# leds.net
KiCad netlist of a schematic drawn in Altium Designer
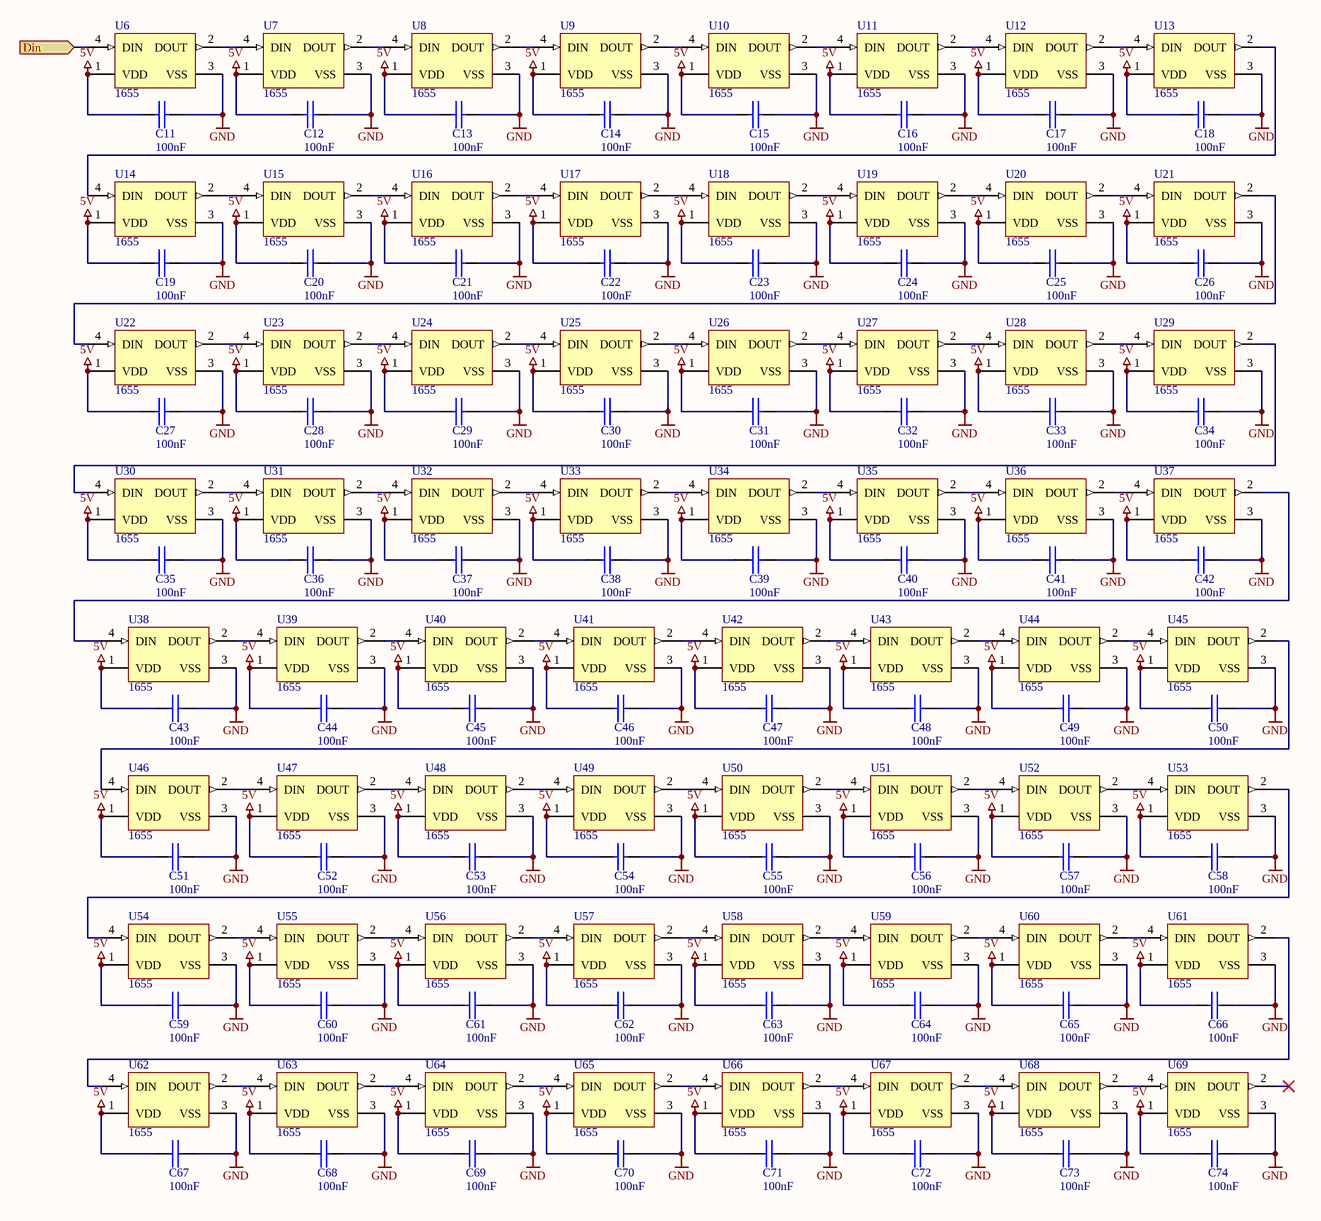
[diagram p0: leds.SchDoc]

(export (version "E")
  (design (tool "Eeschema 10.0.6"))
  (components
    (comp (ref "C11") (value "100nF") (footprint "Cap_0805") (libsource (lib "*") (part "C")))
    (comp (ref "C12") (value "100nF") (footprint "Cap_0805") (libsource (lib "*") (part "C")))
    (comp (ref "C13") (value "100nF") (footprint "Cap_0805") (libsource (lib "*") (part "C")))
    (comp (ref "C14") (value "100nF") (footprint "Cap_0805") (libsource (lib "*") (part "C")))
    (comp (ref "C15") (value "100nF") (footprint "Cap_0805") (libsource (lib "*") (part "C")))
    (comp (ref "C16") (value "100nF") (footprint "Cap_0805") (libsource (lib "*") (part "C")))
    (comp (ref "C17") (value "100nF") (footprint "Cap_0805") (libsource (lib "*") (part "C")))
    (comp (ref "C18") (value "100nF") (footprint "Cap_0805") (libsource (lib "*") (part "C")))
    (comp (ref "C19") (value "100nF") (footprint "Cap_0805") (libsource (lib "*") (part "C")))
    (comp (ref "C20") (value "100nF") (footprint "Cap_0805") (libsource (lib "*") (part "C")))
    (comp (ref "C21") (value "100nF") (footprint "Cap_0805") (libsource (lib "*") (part "C")))
    (comp (ref "C22") (value "100nF") (footprint "Cap_0805") (libsource (lib "*") (part "C")))
    (comp (ref "C23") (value "100nF") (footprint "Cap_0805") (libsource (lib "*") (part "C")))
    (comp (ref "C24") (value "100nF") (footprint "Cap_0805") (libsource (lib "*") (part "C")))
    (comp (ref "C25") (value "100nF") (footprint "Cap_0805") (libsource (lib "*") (part "C")))
    (comp (ref "C26") (value "100nF") (footprint "Cap_0805") (libsource (lib "*") (part "C")))
    (comp (ref "C27") (value "100nF") (footprint "Cap_0805") (libsource (lib "*") (part "C")))
    (comp (ref "C28") (value "100nF") (footprint "Cap_0805") (libsource (lib "*") (part "C")))
    (comp (ref "C29") (value "100nF") (footprint "Cap_0805") (libsource (lib "*") (part "C")))
    (comp (ref "C30") (value "100nF") (footprint "Cap_0805") (libsource (lib "*") (part "C")))
    (comp (ref "C31") (value "100nF") (footprint "Cap_0805") (libsource (lib "*") (part "C")))
    (comp (ref "C32") (value "100nF") (footprint "Cap_0805") (libsource (lib "*") (part "C")))
    (comp (ref "C33") (value "100nF") (footprint "Cap_0805") (libsource (lib "*") (part "C")))
    (comp (ref "C34") (value "100nF") (footprint "Cap_0805") (libsource (lib "*") (part "C")))
    (comp (ref "C35") (value "100nF") (footprint "Cap_0805") (libsource (lib "*") (part "C")))
    (comp (ref "C36") (value "100nF") (footprint "Cap_0805") (libsource (lib "*") (part "C")))
    (comp (ref "C37") (value "100nF") (footprint "Cap_0805") (libsource (lib "*") (part "C")))
    (comp (ref "C38") (value "100nF") (footprint "Cap_0805") (libsource (lib "*") (part "C")))
    (comp (ref "C39") (value "100nF") (footprint "Cap_0805") (libsource (lib "*") (part "C")))
    (comp (ref "C40") (value "100nF") (footprint "Cap_0805") (libsource (lib "*") (part "C")))
    (comp (ref "C41") (value "100nF") (footprint "Cap_0805") (libsource (lib "*") (part "C")))
    (comp (ref "C42") (value "100nF") (footprint "Cap_0805") (libsource (lib "*") (part "C")))
    (comp (ref "C43") (value "100nF") (footprint "Cap_0805") (libsource (lib "*") (part "C")))
    (comp (ref "C44") (value "100nF") (footprint "Cap_0805") (libsource (lib "*") (part "C")))
    (comp (ref "C45") (value "100nF") (footprint "Cap_0805") (libsource (lib "*") (part "C")))
    (comp (ref "C46") (value "100nF") (footprint "Cap_0805") (libsource (lib "*") (part "C")))
    (comp (ref "C47") (value "100nF") (footprint "Cap_0805") (libsource (lib "*") (part "C")))
    (comp (ref "C48") (value "100nF") (footprint "Cap_0805") (libsource (lib "*") (part "C")))
    (comp (ref "C49") (value "100nF") (footprint "Cap_0805") (libsource (lib "*") (part "C")))
    (comp (ref "C50") (value "100nF") (footprint "Cap_0805") (libsource (lib "*") (part "C")))
    (comp (ref "C51") (value "100nF") (footprint "Cap_0805") (libsource (lib "*") (part "C")))
    (comp (ref "C52") (value "100nF") (footprint "Cap_0805") (libsource (lib "*") (part "C")))
    (comp (ref "C53") (value "100nF") (footprint "Cap_0805") (libsource (lib "*") (part "C")))
    (comp (ref "C54") (value "100nF") (footprint "Cap_0805") (libsource (lib "*") (part "C")))
    (comp (ref "C55") (value "100nF") (footprint "Cap_0805") (libsource (lib "*") (part "C")))
    (comp (ref "C56") (value "100nF") (footprint "Cap_0805") (libsource (lib "*") (part "C")))
    (comp (ref "C57") (value "100nF") (footprint "Cap_0805") (libsource (lib "*") (part "C")))
    (comp (ref "C58") (value "100nF") (footprint "Cap_0805") (libsource (lib "*") (part "C")))
    (comp (ref "C59") (value "100nF") (footprint "Cap_0805") (libsource (lib "*") (part "C")))
    (comp (ref "C60") (value "100nF") (footprint "Cap_0805") (libsource (lib "*") (part "C")))
    (comp (ref "C61") (value "100nF") (footprint "Cap_0805") (libsource (lib "*") (part "C")))
    (comp (ref "C62") (value "100nF") (footprint "Cap_0805") (libsource (lib "*") (part "C")))
    (comp (ref "C63") (value "100nF") (footprint "Cap_0805") (libsource (lib "*") (part "C")))
    (comp (ref "C64") (value "100nF") (footprint "Cap_0805") (libsource (lib "*") (part "C")))
    (comp (ref "C65") (value "100nF") (footprint "Cap_0805") (libsource (lib "*") (part "C")))
    (comp (ref "C66") (value "100nF") (footprint "Cap_0805") (libsource (lib "*") (part "C")))
    (comp (ref "C67") (value "100nF") (footprint "Cap_0805") (libsource (lib "*") (part "C")))
    (comp (ref "C68") (value "100nF") (footprint "Cap_0805") (libsource (lib "*") (part "C")))
    (comp (ref "C69") (value "100nF") (footprint "Cap_0805") (libsource (lib "*") (part "C")))
    (comp (ref "C70") (value "100nF") (footprint "Cap_0805") (libsource (lib "*") (part "C")))
    (comp (ref "C71") (value "100nF") (footprint "Cap_0805") (libsource (lib "*") (part "C")))
    (comp (ref "C72") (value "100nF") (footprint "Cap_0805") (libsource (lib "*") (part "C")))
    (comp (ref "C73") (value "100nF") (footprint "Cap_0805") (libsource (lib "*") (part "C")))
    (comp (ref "C74") (value "100nF") (footprint "Cap_0805") (libsource (lib "*") (part "C")))
    (comp (ref "U6")
      (value "1655")
      (footprint "ADA-RGB-1655_V")
      (fields (field (name "MANUFACTURER") "Adafruit-Industries-LLC"))
      (libsource (lib "Altium Content Vault") (part "ADA-RGB-1655-4"))
    )
    (comp (ref "U7")
      (value "1655")
      (footprint "ADA-RGB-1655_V")
      (fields (field (name "MANUFACTURER") "Adafruit-Industries-LLC"))
      (libsource (lib "Altium Content Vault") (part "ADA-RGB-1655-4"))
    )
    (comp (ref "U8")
      (value "1655")
      (footprint "ADA-RGB-1655_V")
      (fields (field (name "MANUFACTURER") "Adafruit-Industries-LLC"))
      (libsource (lib "Altium Content Vault") (part "ADA-RGB-1655-4"))
    )
    (comp (ref "U9")
      (value "1655")
      (footprint "ADA-RGB-1655_V")
      (fields (field (name "MANUFACTURER") "Adafruit-Industries-LLC"))
      (libsource (lib "Altium Content Vault") (part "ADA-RGB-1655-4"))
    )
    (comp (ref "U10")
      (value "1655")
      (footprint "ADA-RGB-1655_V")
      (fields (field (name "MANUFACTURER") "Adafruit-Industries-LLC"))
      (libsource (lib "Altium Content Vault") (part "ADA-RGB-1655-4"))
    )
    (comp (ref "U11")
      (value "1655")
      (footprint "ADA-RGB-1655_V")
      (fields (field (name "MANUFACTURER") "Adafruit-Industries-LLC"))
      (libsource (lib "Altium Content Vault") (part "ADA-RGB-1655-4"))
    )
    (comp (ref "U12")
      (value "1655")
      (footprint "ADA-RGB-1655_V")
      (fields (field (name "MANUFACTURER") "Adafruit-Industries-LLC"))
      (libsource (lib "Altium Content Vault") (part "ADA-RGB-1655-4"))
    )
    (comp (ref "U13")
      (value "1655")
      (footprint "ADA-RGB-1655_V")
      (fields (field (name "MANUFACTURER") "Adafruit-Industries-LLC"))
      (libsource (lib "Altium Content Vault") (part "ADA-RGB-1655-4"))
    )
    (comp (ref "U14")
      (value "1655")
      (footprint "ADA-RGB-1655_V")
      (fields (field (name "MANUFACTURER") "Adafruit-Industries-LLC"))
      (libsource (lib "Altium Content Vault") (part "ADA-RGB-1655-4"))
    )
    (comp (ref "U15")
      (value "1655")
      (footprint "ADA-RGB-1655_V")
      (fields (field (name "MANUFACTURER") "Adafruit-Industries-LLC"))
      (libsource (lib "Altium Content Vault") (part "ADA-RGB-1655-4"))
    )
    (comp (ref "U16")
      (value "1655")
      (footprint "ADA-RGB-1655_V")
      (fields (field (name "MANUFACTURER") "Adafruit-Industries-LLC"))
      (libsource (lib "Altium Content Vault") (part "ADA-RGB-1655-4"))
    )
    (comp (ref "U17")
      (value "1655")
      (footprint "ADA-RGB-1655_V")
      (fields (field (name "MANUFACTURER") "Adafruit-Industries-LLC"))
      (libsource (lib "Altium Content Vault") (part "ADA-RGB-1655-4"))
    )
    (comp (ref "U18")
      (value "1655")
      (footprint "ADA-RGB-1655_V")
      (fields (field (name "MANUFACTURER") "Adafruit-Industries-LLC"))
      (libsource (lib "Altium Content Vault") (part "ADA-RGB-1655-4"))
    )
    (comp (ref "U19")
      (value "1655")
      (footprint "ADA-RGB-1655_V")
      (fields (field (name "MANUFACTURER") "Adafruit-Industries-LLC"))
      (libsource (lib "Altium Content Vault") (part "ADA-RGB-1655-4"))
    )
    (comp (ref "U20")
      (value "1655")
      (footprint "ADA-RGB-1655_V")
      (fields (field (name "MANUFACTURER") "Adafruit-Industries-LLC"))
      (libsource (lib "Altium Content Vault") (part "ADA-RGB-1655-4"))
    )
    (comp (ref "U21")
      (value "1655")
      (footprint "ADA-RGB-1655_V")
      (fields (field (name "MANUFACTURER") "Adafruit-Industries-LLC"))
      (libsource (lib "Altium Content Vault") (part "ADA-RGB-1655-4"))
    )
    (comp (ref "U22")
      (value "1655")
      (footprint "ADA-RGB-1655_V")
      (fields (field (name "MANUFACTURER") "Adafruit-Industries-LLC"))
      (libsource (lib "Altium Content Vault") (part "ADA-RGB-1655-4"))
    )
    (comp (ref "U23")
      (value "1655")
      (footprint "ADA-RGB-1655_V")
      (fields (field (name "MANUFACTURER") "Adafruit-Industries-LLC"))
      (libsource (lib "Altium Content Vault") (part "ADA-RGB-1655-4"))
    )
    (comp (ref "U24")
      (value "1655")
      (footprint "ADA-RGB-1655_V")
      (fields (field (name "MANUFACTURER") "Adafruit-Industries-LLC"))
      (libsource (lib "Altium Content Vault") (part "ADA-RGB-1655-4"))
    )
    (comp (ref "U25")
      (value "1655")
      (footprint "ADA-RGB-1655_V")
      (fields (field (name "MANUFACTURER") "Adafruit-Industries-LLC"))
      (libsource (lib "Altium Content Vault") (part "ADA-RGB-1655-4"))
    )
    (comp (ref "U26")
      (value "1655")
      (footprint "ADA-RGB-1655_V")
      (fields (field (name "MANUFACTURER") "Adafruit-Industries-LLC"))
      (libsource (lib "Altium Content Vault") (part "ADA-RGB-1655-4"))
    )
    (comp (ref "U27")
      (value "1655")
      (footprint "ADA-RGB-1655_V")
      (fields (field (name "MANUFACTURER") "Adafruit-Industries-LLC"))
      (libsource (lib "Altium Content Vault") (part "ADA-RGB-1655-4"))
    )
    (comp (ref "U28")
      (value "1655")
      (footprint "ADA-RGB-1655_V")
      (fields (field (name "MANUFACTURER") "Adafruit-Industries-LLC"))
      (libsource (lib "Altium Content Vault") (part "ADA-RGB-1655-4"))
    )
    (comp (ref "U29")
      (value "1655")
      (footprint "ADA-RGB-1655_V")
      (fields (field (name "MANUFACTURER") "Adafruit-Industries-LLC"))
      (libsource (lib "Altium Content Vault") (part "ADA-RGB-1655-4"))
    )
    (comp (ref "U30")
      (value "1655")
      (footprint "ADA-RGB-1655_V")
      (fields (field (name "MANUFACTURER") "Adafruit-Industries-LLC"))
      (libsource (lib "Altium Content Vault") (part "ADA-RGB-1655-4"))
    )
    (comp (ref "U31")
      (value "1655")
      (footprint "ADA-RGB-1655_V")
      (fields (field (name "MANUFACTURER") "Adafruit-Industries-LLC"))
      (libsource (lib "Altium Content Vault") (part "ADA-RGB-1655-4"))
    )
    (comp (ref "U32")
      (value "1655")
      (footprint "ADA-RGB-1655_V")
      (fields (field (name "MANUFACTURER") "Adafruit-Industries-LLC"))
      (libsource (lib "Altium Content Vault") (part "ADA-RGB-1655-4"))
    )
    (comp (ref "U33")
      (value "1655")
      (footprint "ADA-RGB-1655_V")
      (fields (field (name "MANUFACTURER") "Adafruit-Industries-LLC"))
      (libsource (lib "Altium Content Vault") (part "ADA-RGB-1655-4"))
    )
    (comp (ref "U34")
      (value "1655")
      (footprint "ADA-RGB-1655_V")
      (fields (field (name "MANUFACTURER") "Adafruit-Industries-LLC"))
      (libsource (lib "Altium Content Vault") (part "ADA-RGB-1655-4"))
    )
    (comp (ref "U35")
      (value "1655")
      (footprint "ADA-RGB-1655_V")
      (fields (field (name "MANUFACTURER") "Adafruit-Industries-LLC"))
      (libsource (lib "Altium Content Vault") (part "ADA-RGB-1655-4"))
    )
    (comp (ref "U36")
      (value "1655")
      (footprint "ADA-RGB-1655_V")
      (fields (field (name "MANUFACTURER") "Adafruit-Industries-LLC"))
      (libsource (lib "Altium Content Vault") (part "ADA-RGB-1655-4"))
    )
    (comp (ref "U37")
      (value "1655")
      (footprint "ADA-RGB-1655_V")
      (fields (field (name "MANUFACTURER") "Adafruit-Industries-LLC"))
      (libsource (lib "Altium Content Vault") (part "ADA-RGB-1655-4"))
    )
    (comp (ref "U38")
      (value "1655")
      (footprint "ADA-RGB-1655_V")
      (fields (field (name "MANUFACTURER") "Adafruit-Industries-LLC"))
      (libsource (lib "Altium Content Vault") (part "ADA-RGB-1655-4"))
    )
    (comp (ref "U39")
      (value "1655")
      (footprint "ADA-RGB-1655_V")
      (fields (field (name "MANUFACTURER") "Adafruit-Industries-LLC"))
      (libsource (lib "Altium Content Vault") (part "ADA-RGB-1655-4"))
    )
    (comp (ref "U40")
      (value "1655")
      (footprint "ADA-RGB-1655_V")
      (fields (field (name "MANUFACTURER") "Adafruit-Industries-LLC"))
      (libsource (lib "Altium Content Vault") (part "ADA-RGB-1655-4"))
    )
    (comp (ref "U41")
      (value "1655")
      (footprint "ADA-RGB-1655_V")
      (fields (field (name "MANUFACTURER") "Adafruit-Industries-LLC"))
      (libsource (lib "Altium Content Vault") (part "ADA-RGB-1655-4"))
    )
    (comp (ref "U42")
      (value "1655")
      (footprint "ADA-RGB-1655_V")
      (fields (field (name "MANUFACTURER") "Adafruit-Industries-LLC"))
      (libsource (lib "Altium Content Vault") (part "ADA-RGB-1655-4"))
    )
    (comp (ref "U43")
      (value "1655")
      (footprint "ADA-RGB-1655_V")
      (fields (field (name "MANUFACTURER") "Adafruit-Industries-LLC"))
      (libsource (lib "Altium Content Vault") (part "ADA-RGB-1655-4"))
    )
    (comp (ref "U44")
      (value "1655")
      (footprint "ADA-RGB-1655_V")
      (fields (field (name "MANUFACTURER") "Adafruit-Industries-LLC"))
      (libsource (lib "Altium Content Vault") (part "ADA-RGB-1655-4"))
    )
    (comp (ref "U45")
      (value "1655")
      (footprint "ADA-RGB-1655_V")
      (fields (field (name "MANUFACTURER") "Adafruit-Industries-LLC"))
      (libsource (lib "Altium Content Vault") (part "ADA-RGB-1655-4"))
    )
    (comp (ref "U46")
      (value "1655")
      (footprint "ADA-RGB-1655_V")
      (fields (field (name "MANUFACTURER") "Adafruit-Industries-LLC"))
      (libsource (lib "Altium Content Vault") (part "ADA-RGB-1655-4"))
    )
    (comp (ref "U47")
      (value "1655")
      (footprint "ADA-RGB-1655_V")
      (fields (field (name "MANUFACTURER") "Adafruit-Industries-LLC"))
      (libsource (lib "Altium Content Vault") (part "ADA-RGB-1655-4"))
    )
    (comp (ref "U48")
      (value "1655")
      (footprint "ADA-RGB-1655_V")
      (fields (field (name "MANUFACTURER") "Adafruit-Industries-LLC"))
      (libsource (lib "Altium Content Vault") (part "ADA-RGB-1655-4"))
    )
    (comp (ref "U49")
      (value "1655")
      (footprint "ADA-RGB-1655_V")
      (fields (field (name "MANUFACTURER") "Adafruit-Industries-LLC"))
      (libsource (lib "Altium Content Vault") (part "ADA-RGB-1655-4"))
    )
    (comp (ref "U50")
      (value "1655")
      (footprint "ADA-RGB-1655_V")
      (fields (field (name "MANUFACTURER") "Adafruit-Industries-LLC"))
      (libsource (lib "Altium Content Vault") (part "ADA-RGB-1655-4"))
    )
    (comp (ref "U51")
      (value "1655")
      (footprint "ADA-RGB-1655_V")
      (fields (field (name "MANUFACTURER") "Adafruit-Industries-LLC"))
      (libsource (lib "Altium Content Vault") (part "ADA-RGB-1655-4"))
    )
    (comp (ref "U52")
      (value "1655")
      (footprint "ADA-RGB-1655_V")
      (fields (field (name "MANUFACTURER") "Adafruit-Industries-LLC"))
      (libsource (lib "Altium Content Vault") (part "ADA-RGB-1655-4"))
    )
    (comp (ref "U53")
      (value "1655")
      (footprint "ADA-RGB-1655_V")
      (fields (field (name "MANUFACTURER") "Adafruit-Industries-LLC"))
      (libsource (lib "Altium Content Vault") (part "ADA-RGB-1655-4"))
    )
    (comp (ref "U54")
      (value "1655")
      (footprint "ADA-RGB-1655_V")
      (fields (field (name "MANUFACTURER") "Adafruit-Industries-LLC"))
      (libsource (lib "Altium Content Vault") (part "ADA-RGB-1655-4"))
    )
    (comp (ref "U55")
      (value "1655")
      (footprint "ADA-RGB-1655_V")
      (fields (field (name "MANUFACTURER") "Adafruit-Industries-LLC"))
      (libsource (lib "Altium Content Vault") (part "ADA-RGB-1655-4"))
    )
    (comp (ref "U56")
      (value "1655")
      (footprint "ADA-RGB-1655_V")
      (fields (field (name "MANUFACTURER") "Adafruit-Industries-LLC"))
      (libsource (lib "Altium Content Vault") (part "ADA-RGB-1655-4"))
    )
    (comp (ref "U57")
      (value "1655")
      (footprint "ADA-RGB-1655_V")
      (fields (field (name "MANUFACTURER") "Adafruit-Industries-LLC"))
      (libsource (lib "Altium Content Vault") (part "ADA-RGB-1655-4"))
    )
    (comp (ref "U58")
      (value "1655")
      (footprint "ADA-RGB-1655_V")
      (fields (field (name "MANUFACTURER") "Adafruit-Industries-LLC"))
      (libsource (lib "Altium Content Vault") (part "ADA-RGB-1655-4"))
    )
    (comp (ref "U59")
      (value "1655")
      (footprint "ADA-RGB-1655_V")
      (fields (field (name "MANUFACTURER") "Adafruit-Industries-LLC"))
      (libsource (lib "Altium Content Vault") (part "ADA-RGB-1655-4"))
    )
    (comp (ref "U60")
      (value "1655")
      (footprint "ADA-RGB-1655_V")
      (fields (field (name "MANUFACTURER") "Adafruit-Industries-LLC"))
      (libsource (lib "Altium Content Vault") (part "ADA-RGB-1655-4"))
    )
    (comp (ref "U61")
      (value "1655")
      (footprint "ADA-RGB-1655_V")
      (fields (field (name "MANUFACTURER") "Adafruit-Industries-LLC"))
      (libsource (lib "Altium Content Vault") (part "ADA-RGB-1655-4"))
    )
    (comp (ref "U62")
      (value "1655")
      (footprint "ADA-RGB-1655_V")
      (fields (field (name "MANUFACTURER") "Adafruit-Industries-LLC"))
      (libsource (lib "Altium Content Vault") (part "ADA-RGB-1655-4"))
    )
    (comp (ref "U63")
      (value "1655")
      (footprint "ADA-RGB-1655_V")
      (fields (field (name "MANUFACTURER") "Adafruit-Industries-LLC"))
      (libsource (lib "Altium Content Vault") (part "ADA-RGB-1655-4"))
    )
    (comp (ref "U64")
      (value "1655")
      (footprint "ADA-RGB-1655_V")
      (fields (field (name "MANUFACTURER") "Adafruit-Industries-LLC"))
      (libsource (lib "Altium Content Vault") (part "ADA-RGB-1655-4"))
    )
    (comp (ref "U65")
      (value "1655")
      (footprint "ADA-RGB-1655_V")
      (fields (field (name "MANUFACTURER") "Adafruit-Industries-LLC"))
      (libsource (lib "Altium Content Vault") (part "ADA-RGB-1655-4"))
    )
    (comp (ref "U66")
      (value "1655")
      (footprint "ADA-RGB-1655_V")
      (fields (field (name "MANUFACTURER") "Adafruit-Industries-LLC"))
      (libsource (lib "Altium Content Vault") (part "ADA-RGB-1655-4"))
    )
    (comp (ref "U67")
      (value "1655")
      (footprint "ADA-RGB-1655_V")
      (fields (field (name "MANUFACTURER") "Adafruit-Industries-LLC"))
      (libsource (lib "Altium Content Vault") (part "ADA-RGB-1655-4"))
    )
    (comp (ref "U68")
      (value "1655")
      (footprint "ADA-RGB-1655_V")
      (fields (field (name "MANUFACTURER") "Adafruit-Industries-LLC"))
      (libsource (lib "Altium Content Vault") (part "ADA-RGB-1655-4"))
    )
    (comp (ref "U69")
      (value "1655")
      (footprint "ADA-RGB-1655_V")
      (fields (field (name "MANUFACTURER") "Adafruit-Industries-LLC"))
      (libsource (lib "Altium Content Vault") (part "ADA-RGB-1655-4"))
    )
  )
  (nets
    (net (code "1") (name "/Din") (class "Default")
      (node (ref "U6") (pin "4") (pinfunction "DIN_4") (pintype "input"))
    )
    (net (code "2") (name "5V") (class "Default")
      (node (ref "C11") (pin "1") (pinfunction "1_1") (pintype "passive"))
      (node (ref "C12") (pin "1") (pinfunction "1_1") (pintype "passive"))
      (node (ref "C13") (pin "1") (pinfunction "1_1") (pintype "passive"))
      (node (ref "C14") (pin "1") (pinfunction "1_1") (pintype "passive"))
      (node (ref "C15") (pin "1") (pinfunction "1_1") (pintype "passive"))
      (node (ref "C16") (pin "1") (pinfunction "1_1") (pintype "passive"))
      (node (ref "C17") (pin "1") (pinfunction "1_1") (pintype "passive"))
      (node (ref "C18") (pin "1") (pinfunction "1_1") (pintype "passive"))
      (node (ref "C19") (pin "1") (pinfunction "1_1") (pintype "passive"))
      (node (ref "C20") (pin "1") (pinfunction "1_1") (pintype "passive"))
      (node (ref "C21") (pin "1") (pinfunction "1_1") (pintype "passive"))
      (node (ref "C22") (pin "1") (pinfunction "1_1") (pintype "passive"))
      (node (ref "C23") (pin "1") (pinfunction "1_1") (pintype "passive"))
      (node (ref "C24") (pin "1") (pinfunction "1_1") (pintype "passive"))
      (node (ref "C25") (pin "1") (pinfunction "1_1") (pintype "passive"))
      (node (ref "C26") (pin "1") (pinfunction "1_1") (pintype "passive"))
      (node (ref "C27") (pin "1") (pinfunction "1_1") (pintype "passive"))
      (node (ref "C28") (pin "1") (pinfunction "1_1") (pintype "passive"))
      (node (ref "C29") (pin "1") (pinfunction "1_1") (pintype "passive"))
      (node (ref "C30") (pin "1") (pinfunction "1_1") (pintype "passive"))
      (node (ref "C31") (pin "1") (pinfunction "1_1") (pintype "passive"))
      (node (ref "C32") (pin "1") (pinfunction "1_1") (pintype "passive"))
      (node (ref "C33") (pin "1") (pinfunction "1_1") (pintype "passive"))
      (node (ref "C34") (pin "1") (pinfunction "1_1") (pintype "passive"))
      (node (ref "C35") (pin "1") (pinfunction "1_1") (pintype "passive"))
      (node (ref "C36") (pin "1") (pinfunction "1_1") (pintype "passive"))
      (node (ref "C37") (pin "1") (pinfunction "1_1") (pintype "passive"))
      (node (ref "C38") (pin "1") (pinfunction "1_1") (pintype "passive"))
      (node (ref "C39") (pin "1") (pinfunction "1_1") (pintype "passive"))
      (node (ref "C40") (pin "1") (pinfunction "1_1") (pintype "passive"))
      (node (ref "C41") (pin "1") (pinfunction "1_1") (pintype "passive"))
      (node (ref "C42") (pin "1") (pinfunction "1_1") (pintype "passive"))
      (node (ref "C43") (pin "1") (pinfunction "1_1") (pintype "passive"))
      (node (ref "C44") (pin "1") (pinfunction "1_1") (pintype "passive"))
      (node (ref "C45") (pin "1") (pinfunction "1_1") (pintype "passive"))
      (node (ref "C46") (pin "1") (pinfunction "1_1") (pintype "passive"))
      (node (ref "C47") (pin "1") (pinfunction "1_1") (pintype "passive"))
      (node (ref "C48") (pin "1") (pinfunction "1_1") (pintype "passive"))
      (node (ref "C49") (pin "1") (pinfunction "1_1") (pintype "passive"))
      (node (ref "C50") (pin "1") (pinfunction "1_1") (pintype "passive"))
      (node (ref "C51") (pin "1") (pinfunction "1_1") (pintype "passive"))
      (node (ref "C52") (pin "1") (pinfunction "1_1") (pintype "passive"))
      (node (ref "C53") (pin "1") (pinfunction "1_1") (pintype "passive"))
      (node (ref "C54") (pin "1") (pinfunction "1_1") (pintype "passive"))
      (node (ref "C55") (pin "1") (pinfunction "1_1") (pintype "passive"))
      (node (ref "C56") (pin "1") (pinfunction "1_1") (pintype "passive"))
      (node (ref "C57") (pin "1") (pinfunction "1_1") (pintype "passive"))
      (node (ref "C58") (pin "1") (pinfunction "1_1") (pintype "passive"))
      (node (ref "C59") (pin "1") (pinfunction "1_1") (pintype "passive"))
      (node (ref "C60") (pin "1") (pinfunction "1_1") (pintype "passive"))
      (node (ref "C61") (pin "1") (pinfunction "1_1") (pintype "passive"))
      (node (ref "C62") (pin "1") (pinfunction "1_1") (pintype "passive"))
      (node (ref "C63") (pin "1") (pinfunction "1_1") (pintype "passive"))
      (node (ref "C64") (pin "1") (pinfunction "1_1") (pintype "passive"))
      (node (ref "C65") (pin "1") (pinfunction "1_1") (pintype "passive"))
      (node (ref "C66") (pin "1") (pinfunction "1_1") (pintype "passive"))
      (node (ref "C67") (pin "1") (pinfunction "1_1") (pintype "passive"))
      (node (ref "C68") (pin "1") (pinfunction "1_1") (pintype "passive"))
      (node (ref "C69") (pin "1") (pinfunction "1_1") (pintype "passive"))
      (node (ref "C70") (pin "1") (pinfunction "1_1") (pintype "passive"))
      (node (ref "C71") (pin "1") (pinfunction "1_1") (pintype "passive"))
      (node (ref "C72") (pin "1") (pinfunction "1_1") (pintype "passive"))
      (node (ref "C73") (pin "1") (pinfunction "1_1") (pintype "passive"))
      (node (ref "C74") (pin "1") (pinfunction "1_1") (pintype "passive"))
      (node (ref "U10") (pin "1") (pinfunction "VDD_1") (pintype "power_in"))
      (node (ref "U11") (pin "1") (pinfunction "VDD_1") (pintype "power_in"))
      (node (ref "U12") (pin "1") (pinfunction "VDD_1") (pintype "power_in"))
      (node (ref "U13") (pin "1") (pinfunction "VDD_1") (pintype "power_in"))
      (node (ref "U14") (pin "1") (pinfunction "VDD_1") (pintype "power_in"))
      (node (ref "U15") (pin "1") (pinfunction "VDD_1") (pintype "power_in"))
      (node (ref "U16") (pin "1") (pinfunction "VDD_1") (pintype "power_in"))
      (node (ref "U17") (pin "1") (pinfunction "VDD_1") (pintype "power_in"))
      (node (ref "U18") (pin "1") (pinfunction "VDD_1") (pintype "power_in"))
      (node (ref "U19") (pin "1") (pinfunction "VDD_1") (pintype "power_in"))
      (node (ref "U20") (pin "1") (pinfunction "VDD_1") (pintype "power_in"))
      (node (ref "U21") (pin "1") (pinfunction "VDD_1") (pintype "power_in"))
      (node (ref "U22") (pin "1") (pinfunction "VDD_1") (pintype "power_in"))
      (node (ref "U23") (pin "1") (pinfunction "VDD_1") (pintype "power_in"))
      (node (ref "U24") (pin "1") (pinfunction "VDD_1") (pintype "power_in"))
      (node (ref "U25") (pin "1") (pinfunction "VDD_1") (pintype "power_in"))
      (node (ref "U26") (pin "1") (pinfunction "VDD_1") (pintype "power_in"))
      (node (ref "U27") (pin "1") (pinfunction "VDD_1") (pintype "power_in"))
      (node (ref "U28") (pin "1") (pinfunction "VDD_1") (pintype "power_in"))
      (node (ref "U29") (pin "1") (pinfunction "VDD_1") (pintype "power_in"))
      (node (ref "U30") (pin "1") (pinfunction "VDD_1") (pintype "power_in"))
      (node (ref "U31") (pin "1") (pinfunction "VDD_1") (pintype "power_in"))
      (node (ref "U32") (pin "1") (pinfunction "VDD_1") (pintype "power_in"))
      (node (ref "U33") (pin "1") (pinfunction "VDD_1") (pintype "power_in"))
      (node (ref "U34") (pin "1") (pinfunction "VDD_1") (pintype "power_in"))
      (node (ref "U35") (pin "1") (pinfunction "VDD_1") (pintype "power_in"))
      (node (ref "U36") (pin "1") (pinfunction "VDD_1") (pintype "power_in"))
      (node (ref "U37") (pin "1") (pinfunction "VDD_1") (pintype "power_in"))
      (node (ref "U38") (pin "1") (pinfunction "VDD_1") (pintype "power_in"))
      (node (ref "U39") (pin "1") (pinfunction "VDD_1") (pintype "power_in"))
      (node (ref "U40") (pin "1") (pinfunction "VDD_1") (pintype "power_in"))
      (node (ref "U41") (pin "1") (pinfunction "VDD_1") (pintype "power_in"))
      (node (ref "U42") (pin "1") (pinfunction "VDD_1") (pintype "power_in"))
      (node (ref "U43") (pin "1") (pinfunction "VDD_1") (pintype "power_in"))
      (node (ref "U44") (pin "1") (pinfunction "VDD_1") (pintype "power_in"))
      (node (ref "U45") (pin "1") (pinfunction "VDD_1") (pintype "power_in"))
      (node (ref "U46") (pin "1") (pinfunction "VDD_1") (pintype "power_in"))
      (node (ref "U47") (pin "1") (pinfunction "VDD_1") (pintype "power_in"))
      (node (ref "U48") (pin "1") (pinfunction "VDD_1") (pintype "power_in"))
      (node (ref "U49") (pin "1") (pinfunction "VDD_1") (pintype "power_in"))
      (node (ref "U50") (pin "1") (pinfunction "VDD_1") (pintype "power_in"))
      (node (ref "U51") (pin "1") (pinfunction "VDD_1") (pintype "power_in"))
      (node (ref "U52") (pin "1") (pinfunction "VDD_1") (pintype "power_in"))
      (node (ref "U53") (pin "1") (pinfunction "VDD_1") (pintype "power_in"))
      (node (ref "U54") (pin "1") (pinfunction "VDD_1") (pintype "power_in"))
      (node (ref "U55") (pin "1") (pinfunction "VDD_1") (pintype "power_in"))
      (node (ref "U56") (pin "1") (pinfunction "VDD_1") (pintype "power_in"))
      (node (ref "U57") (pin "1") (pinfunction "VDD_1") (pintype "power_in"))
      (node (ref "U58") (pin "1") (pinfunction "VDD_1") (pintype "power_in"))
      (node (ref "U59") (pin "1") (pinfunction "VDD_1") (pintype "power_in"))
      (node (ref "U6") (pin "1") (pinfunction "VDD_1") (pintype "power_in"))
      (node (ref "U60") (pin "1") (pinfunction "VDD_1") (pintype "power_in"))
      (node (ref "U61") (pin "1") (pinfunction "VDD_1") (pintype "power_in"))
      (node (ref "U62") (pin "1") (pinfunction "VDD_1") (pintype "power_in"))
      (node (ref "U63") (pin "1") (pinfunction "VDD_1") (pintype "power_in"))
      (node (ref "U64") (pin "1") (pinfunction "VDD_1") (pintype "power_in"))
      (node (ref "U65") (pin "1") (pinfunction "VDD_1") (pintype "power_in"))
      (node (ref "U66") (pin "1") (pinfunction "VDD_1") (pintype "power_in"))
      (node (ref "U67") (pin "1") (pinfunction "VDD_1") (pintype "power_in"))
      (node (ref "U68") (pin "1") (pinfunction "VDD_1") (pintype "power_in"))
      (node (ref "U69") (pin "1") (pinfunction "VDD_1") (pintype "power_in"))
      (node (ref "U7") (pin "1") (pinfunction "VDD_1") (pintype "power_in"))
      (node (ref "U8") (pin "1") (pinfunction "VDD_1") (pintype "power_in"))
      (node (ref "U9") (pin "1") (pinfunction "VDD_1") (pintype "power_in"))
    )
    (net (code "3") (name "GND") (class "Default")
      (node (ref "C11") (pin "2") (pinfunction "2_2") (pintype "passive"))
      (node (ref "C12") (pin "2") (pinfunction "2_2") (pintype "passive"))
      (node (ref "C13") (pin "2") (pinfunction "2_2") (pintype "passive"))
      (node (ref "C14") (pin "2") (pinfunction "2_2") (pintype "passive"))
      (node (ref "C15") (pin "2") (pinfunction "2_2") (pintype "passive"))
      (node (ref "C16") (pin "2") (pinfunction "2_2") (pintype "passive"))
      (node (ref "C17") (pin "2") (pinfunction "2_2") (pintype "passive"))
      (node (ref "C18") (pin "2") (pinfunction "2_2") (pintype "passive"))
      (node (ref "C19") (pin "2") (pinfunction "2_2") (pintype "passive"))
      (node (ref "C20") (pin "2") (pinfunction "2_2") (pintype "passive"))
      (node (ref "C21") (pin "2") (pinfunction "2_2") (pintype "passive"))
      (node (ref "C22") (pin "2") (pinfunction "2_2") (pintype "passive"))
      (node (ref "C23") (pin "2") (pinfunction "2_2") (pintype "passive"))
      (node (ref "C24") (pin "2") (pinfunction "2_2") (pintype "passive"))
      (node (ref "C25") (pin "2") (pinfunction "2_2") (pintype "passive"))
      (node (ref "C26") (pin "2") (pinfunction "2_2") (pintype "passive"))
      (node (ref "C27") (pin "2") (pinfunction "2_2") (pintype "passive"))
      (node (ref "C28") (pin "2") (pinfunction "2_2") (pintype "passive"))
      (node (ref "C29") (pin "2") (pinfunction "2_2") (pintype "passive"))
      (node (ref "C30") (pin "2") (pinfunction "2_2") (pintype "passive"))
      (node (ref "C31") (pin "2") (pinfunction "2_2") (pintype "passive"))
      (node (ref "C32") (pin "2") (pinfunction "2_2") (pintype "passive"))
      (node (ref "C33") (pin "2") (pinfunction "2_2") (pintype "passive"))
      (node (ref "C34") (pin "2") (pinfunction "2_2") (pintype "passive"))
      (node (ref "C35") (pin "2") (pinfunction "2_2") (pintype "passive"))
      (node (ref "C36") (pin "2") (pinfunction "2_2") (pintype "passive"))
      (node (ref "C37") (pin "2") (pinfunction "2_2") (pintype "passive"))
      (node (ref "C38") (pin "2") (pinfunction "2_2") (pintype "passive"))
      (node (ref "C39") (pin "2") (pinfunction "2_2") (pintype "passive"))
      (node (ref "C40") (pin "2") (pinfunction "2_2") (pintype "passive"))
      (node (ref "C41") (pin "2") (pinfunction "2_2") (pintype "passive"))
      (node (ref "C42") (pin "2") (pinfunction "2_2") (pintype "passive"))
      (node (ref "C43") (pin "2") (pinfunction "2_2") (pintype "passive"))
      (node (ref "C44") (pin "2") (pinfunction "2_2") (pintype "passive"))
      (node (ref "C45") (pin "2") (pinfunction "2_2") (pintype "passive"))
      (node (ref "C46") (pin "2") (pinfunction "2_2") (pintype "passive"))
      (node (ref "C47") (pin "2") (pinfunction "2_2") (pintype "passive"))
      (node (ref "C48") (pin "2") (pinfunction "2_2") (pintype "passive"))
      (node (ref "C49") (pin "2") (pinfunction "2_2") (pintype "passive"))
      (node (ref "C50") (pin "2") (pinfunction "2_2") (pintype "passive"))
      (node (ref "C51") (pin "2") (pinfunction "2_2") (pintype "passive"))
      (node (ref "C52") (pin "2") (pinfunction "2_2") (pintype "passive"))
      (node (ref "C53") (pin "2") (pinfunction "2_2") (pintype "passive"))
      (node (ref "C54") (pin "2") (pinfunction "2_2") (pintype "passive"))
      (node (ref "C55") (pin "2") (pinfunction "2_2") (pintype "passive"))
      (node (ref "C56") (pin "2") (pinfunction "2_2") (pintype "passive"))
      (node (ref "C57") (pin "2") (pinfunction "2_2") (pintype "passive"))
      (node (ref "C58") (pin "2") (pinfunction "2_2") (pintype "passive"))
      (node (ref "C59") (pin "2") (pinfunction "2_2") (pintype "passive"))
      (node (ref "C60") (pin "2") (pinfunction "2_2") (pintype "passive"))
      (node (ref "C61") (pin "2") (pinfunction "2_2") (pintype "passive"))
      (node (ref "C62") (pin "2") (pinfunction "2_2") (pintype "passive"))
      (node (ref "C63") (pin "2") (pinfunction "2_2") (pintype "passive"))
      (node (ref "C64") (pin "2") (pinfunction "2_2") (pintype "passive"))
      (node (ref "C65") (pin "2") (pinfunction "2_2") (pintype "passive"))
      (node (ref "C66") (pin "2") (pinfunction "2_2") (pintype "passive"))
      (node (ref "C67") (pin "2") (pinfunction "2_2") (pintype "passive"))
      (node (ref "C68") (pin "2") (pinfunction "2_2") (pintype "passive"))
      (node (ref "C69") (pin "2") (pinfunction "2_2") (pintype "passive"))
      (node (ref "C70") (pin "2") (pinfunction "2_2") (pintype "passive"))
      (node (ref "C71") (pin "2") (pinfunction "2_2") (pintype "passive"))
      (node (ref "C72") (pin "2") (pinfunction "2_2") (pintype "passive"))
      (node (ref "C73") (pin "2") (pinfunction "2_2") (pintype "passive"))
      (node (ref "C74") (pin "2") (pinfunction "2_2") (pintype "passive"))
      (node (ref "U10") (pin "3") (pinfunction "VSS_3") (pintype "power_in"))
      (node (ref "U11") (pin "3") (pinfunction "VSS_3") (pintype "power_in"))
      (node (ref "U12") (pin "3") (pinfunction "VSS_3") (pintype "power_in"))
      (node (ref "U13") (pin "3") (pinfunction "VSS_3") (pintype "power_in"))
      (node (ref "U14") (pin "3") (pinfunction "VSS_3") (pintype "power_in"))
      (node (ref "U15") (pin "3") (pinfunction "VSS_3") (pintype "power_in"))
      (node (ref "U16") (pin "3") (pinfunction "VSS_3") (pintype "power_in"))
      (node (ref "U17") (pin "3") (pinfunction "VSS_3") (pintype "power_in"))
      (node (ref "U18") (pin "3") (pinfunction "VSS_3") (pintype "power_in"))
      (node (ref "U19") (pin "3") (pinfunction "VSS_3") (pintype "power_in"))
      (node (ref "U20") (pin "3") (pinfunction "VSS_3") (pintype "power_in"))
      (node (ref "U21") (pin "3") (pinfunction "VSS_3") (pintype "power_in"))
      (node (ref "U22") (pin "3") (pinfunction "VSS_3") (pintype "power_in"))
      (node (ref "U23") (pin "3") (pinfunction "VSS_3") (pintype "power_in"))
      (node (ref "U24") (pin "3") (pinfunction "VSS_3") (pintype "power_in"))
      (node (ref "U25") (pin "3") (pinfunction "VSS_3") (pintype "power_in"))
      (node (ref "U26") (pin "3") (pinfunction "VSS_3") (pintype "power_in"))
      (node (ref "U27") (pin "3") (pinfunction "VSS_3") (pintype "power_in"))
      (node (ref "U28") (pin "3") (pinfunction "VSS_3") (pintype "power_in"))
      (node (ref "U29") (pin "3") (pinfunction "VSS_3") (pintype "power_in"))
      (node (ref "U30") (pin "3") (pinfunction "VSS_3") (pintype "power_in"))
      (node (ref "U31") (pin "3") (pinfunction "VSS_3") (pintype "power_in"))
      (node (ref "U32") (pin "3") (pinfunction "VSS_3") (pintype "power_in"))
      (node (ref "U33") (pin "3") (pinfunction "VSS_3") (pintype "power_in"))
      (node (ref "U34") (pin "3") (pinfunction "VSS_3") (pintype "power_in"))
      (node (ref "U35") (pin "3") (pinfunction "VSS_3") (pintype "power_in"))
      (node (ref "U36") (pin "3") (pinfunction "VSS_3") (pintype "power_in"))
      (node (ref "U37") (pin "3") (pinfunction "VSS_3") (pintype "power_in"))
      (node (ref "U38") (pin "3") (pinfunction "VSS_3") (pintype "power_in"))
      (node (ref "U39") (pin "3") (pinfunction "VSS_3") (pintype "power_in"))
      (node (ref "U40") (pin "3") (pinfunction "VSS_3") (pintype "power_in"))
      (node (ref "U41") (pin "3") (pinfunction "VSS_3") (pintype "power_in"))
      (node (ref "U42") (pin "3") (pinfunction "VSS_3") (pintype "power_in"))
      (node (ref "U43") (pin "3") (pinfunction "VSS_3") (pintype "power_in"))
      (node (ref "U44") (pin "3") (pinfunction "VSS_3") (pintype "power_in"))
      (node (ref "U45") (pin "3") (pinfunction "VSS_3") (pintype "power_in"))
      (node (ref "U46") (pin "3") (pinfunction "VSS_3") (pintype "power_in"))
      (node (ref "U47") (pin "3") (pinfunction "VSS_3") (pintype "power_in"))
      (node (ref "U48") (pin "3") (pinfunction "VSS_3") (pintype "power_in"))
      (node (ref "U49") (pin "3") (pinfunction "VSS_3") (pintype "power_in"))
      (node (ref "U50") (pin "3") (pinfunction "VSS_3") (pintype "power_in"))
      (node (ref "U51") (pin "3") (pinfunction "VSS_3") (pintype "power_in"))
      (node (ref "U52") (pin "3") (pinfunction "VSS_3") (pintype "power_in"))
      (node (ref "U53") (pin "3") (pinfunction "VSS_3") (pintype "power_in"))
      (node (ref "U54") (pin "3") (pinfunction "VSS_3") (pintype "power_in"))
      (node (ref "U55") (pin "3") (pinfunction "VSS_3") (pintype "power_in"))
      (node (ref "U56") (pin "3") (pinfunction "VSS_3") (pintype "power_in"))
      (node (ref "U57") (pin "3") (pinfunction "VSS_3") (pintype "power_in"))
      (node (ref "U58") (pin "3") (pinfunction "VSS_3") (pintype "power_in"))
      (node (ref "U59") (pin "3") (pinfunction "VSS_3") (pintype "power_in"))
      (node (ref "U6") (pin "3") (pinfunction "VSS_3") (pintype "power_in"))
      (node (ref "U60") (pin "3") (pinfunction "VSS_3") (pintype "power_in"))
      (node (ref "U61") (pin "3") (pinfunction "VSS_3") (pintype "power_in"))
      (node (ref "U62") (pin "3") (pinfunction "VSS_3") (pintype "power_in"))
      (node (ref "U63") (pin "3") (pinfunction "VSS_3") (pintype "power_in"))
      (node (ref "U64") (pin "3") (pinfunction "VSS_3") (pintype "power_in"))
      (node (ref "U65") (pin "3") (pinfunction "VSS_3") (pintype "power_in"))
      (node (ref "U66") (pin "3") (pinfunction "VSS_3") (pintype "power_in"))
      (node (ref "U67") (pin "3") (pinfunction "VSS_3") (pintype "power_in"))
      (node (ref "U68") (pin "3") (pinfunction "VSS_3") (pintype "power_in"))
      (node (ref "U69") (pin "3") (pinfunction "VSS_3") (pintype "power_in"))
      (node (ref "U7") (pin "3") (pinfunction "VSS_3") (pintype "power_in"))
      (node (ref "U8") (pin "3") (pinfunction "VSS_3") (pintype "power_in"))
      (node (ref "U9") (pin "3") (pinfunction "VSS_3") (pintype "power_in"))
    )
    (net (code "4") (name "Net-(U6-DOUT)") (class "Default")
      (node (ref "U6") (pin "2") (pinfunction "DOUT_2") (pintype "output"))
      (node (ref "U7") (pin "4") (pinfunction "DIN_4") (pintype "input"))
    )
    (net (code "5") (name "Net-(U7-DOUT)") (class "Default")
      (node (ref "U7") (pin "2") (pinfunction "DOUT_2") (pintype "output"))
      (node (ref "U8") (pin "4") (pinfunction "DIN_4") (pintype "input"))
    )
    (net (code "6") (name "Net-(U8-DOUT)") (class "Default")
      (node (ref "U8") (pin "2") (pinfunction "DOUT_2") (pintype "output"))
      (node (ref "U9") (pin "4") (pinfunction "DIN_4") (pintype "input"))
    )
    (net (code "7") (name "Net-(U10-DIN)") (class "Default")
      (node (ref "U10") (pin "4") (pinfunction "DIN_4") (pintype "input"))
      (node (ref "U9") (pin "2") (pinfunction "DOUT_2") (pintype "output"))
    )
    (net (code "8") (name "Net-(U10-DOUT)") (class "Default")
      (node (ref "U10") (pin "2") (pinfunction "DOUT_2") (pintype "output"))
      (node (ref "U11") (pin "4") (pinfunction "DIN_4") (pintype "input"))
    )
    (net (code "9") (name "Net-(U11-DOUT)") (class "Default")
      (node (ref "U11") (pin "2") (pinfunction "DOUT_2") (pintype "output"))
      (node (ref "U12") (pin "4") (pinfunction "DIN_4") (pintype "input"))
    )
    (net (code "10") (name "Net-(U12-DOUT)") (class "Default")
      (node (ref "U12") (pin "2") (pinfunction "DOUT_2") (pintype "output"))
      (node (ref "U13") (pin "4") (pinfunction "DIN_4") (pintype "input"))
    )
    (net (code "11") (name "Net-(U13-DOUT)") (class "Default")
      (node (ref "U13") (pin "2") (pinfunction "DOUT_2") (pintype "output"))
      (node (ref "U14") (pin "4") (pinfunction "DIN_4") (pintype "input"))
    )
    (net (code "12") (name "Net-(U14-DOUT)") (class "Default")
      (node (ref "U14") (pin "2") (pinfunction "DOUT_2") (pintype "output"))
      (node (ref "U15") (pin "4") (pinfunction "DIN_4") (pintype "input"))
    )
    (net (code "13") (name "Net-(U15-DOUT)") (class "Default")
      (node (ref "U15") (pin "2") (pinfunction "DOUT_2") (pintype "output"))
      (node (ref "U16") (pin "4") (pinfunction "DIN_4") (pintype "input"))
    )
    (net (code "14") (name "Net-(U16-DOUT)") (class "Default")
      (node (ref "U16") (pin "2") (pinfunction "DOUT_2") (pintype "output"))
      (node (ref "U17") (pin "4") (pinfunction "DIN_4") (pintype "input"))
    )
    (net (code "15") (name "Net-(U17-DOUT)") (class "Default")
      (node (ref "U17") (pin "2") (pinfunction "DOUT_2") (pintype "output"))
      (node (ref "U18") (pin "4") (pinfunction "DIN_4") (pintype "input"))
    )
    (net (code "16") (name "Net-(U18-DOUT)") (class "Default")
      (node (ref "U18") (pin "2") (pinfunction "DOUT_2") (pintype "output"))
      (node (ref "U19") (pin "4") (pinfunction "DIN_4") (pintype "input"))
    )
    (net (code "17") (name "Net-(U19-DOUT)") (class "Default")
      (node (ref "U19") (pin "2") (pinfunction "DOUT_2") (pintype "output"))
      (node (ref "U20") (pin "4") (pinfunction "DIN_4") (pintype "input"))
    )
    (net (code "18") (name "Net-(U20-DOUT)") (class "Default")
      (node (ref "U20") (pin "2") (pinfunction "DOUT_2") (pintype "output"))
      (node (ref "U21") (pin "4") (pinfunction "DIN_4") (pintype "input"))
    )
    (net (code "19") (name "Net-(U21-DOUT)") (class "Default")
      (node (ref "U21") (pin "2") (pinfunction "DOUT_2") (pintype "output"))
      (node (ref "U22") (pin "4") (pinfunction "DIN_4") (pintype "input"))
    )
    (net (code "20") (name "Net-(U22-DOUT)") (class "Default")
      (node (ref "U22") (pin "2") (pinfunction "DOUT_2") (pintype "output"))
      (node (ref "U23") (pin "4") (pinfunction "DIN_4") (pintype "input"))
    )
    (net (code "21") (name "Net-(U23-DOUT)") (class "Default")
      (node (ref "U23") (pin "2") (pinfunction "DOUT_2") (pintype "output"))
      (node (ref "U24") (pin "4") (pinfunction "DIN_4") (pintype "input"))
    )
    (net (code "22") (name "Net-(U24-DOUT)") (class "Default")
      (node (ref "U24") (pin "2") (pinfunction "DOUT_2") (pintype "output"))
      (node (ref "U25") (pin "4") (pinfunction "DIN_4") (pintype "input"))
    )
    (net (code "23") (name "Net-(U25-DOUT)") (class "Default")
      (node (ref "U25") (pin "2") (pinfunction "DOUT_2") (pintype "output"))
      (node (ref "U26") (pin "4") (pinfunction "DIN_4") (pintype "input"))
    )
    (net (code "24") (name "Net-(U26-DOUT)") (class "Default")
      (node (ref "U26") (pin "2") (pinfunction "DOUT_2") (pintype "output"))
      (node (ref "U27") (pin "4") (pinfunction "DIN_4") (pintype "input"))
    )
    (net (code "25") (name "Net-(U27-DOUT)") (class "Default")
      (node (ref "U27") (pin "2") (pinfunction "DOUT_2") (pintype "output"))
      (node (ref "U28") (pin "4") (pinfunction "DIN_4") (pintype "input"))
    )
    (net (code "26") (name "Net-(U28-DOUT)") (class "Default")
      (node (ref "U28") (pin "2") (pinfunction "DOUT_2") (pintype "output"))
      (node (ref "U29") (pin "4") (pinfunction "DIN_4") (pintype "input"))
    )
    (net (code "27") (name "Net-(U29-DOUT)") (class "Default")
      (node (ref "U29") (pin "2") (pinfunction "DOUT_2") (pintype "output"))
      (node (ref "U30") (pin "4") (pinfunction "DIN_4") (pintype "input"))
    )
    (net (code "28") (name "Net-(U30-DOUT)") (class "Default")
      (node (ref "U30") (pin "2") (pinfunction "DOUT_2") (pintype "output"))
      (node (ref "U31") (pin "4") (pinfunction "DIN_4") (pintype "input"))
    )
    (net (code "29") (name "Net-(U31-DOUT)") (class "Default")
      (node (ref "U31") (pin "2") (pinfunction "DOUT_2") (pintype "output"))
      (node (ref "U32") (pin "4") (pinfunction "DIN_4") (pintype "input"))
    )
    (net (code "30") (name "Net-(U32-DOUT)") (class "Default")
      (node (ref "U32") (pin "2") (pinfunction "DOUT_2") (pintype "output"))
      (node (ref "U33") (pin "4") (pinfunction "DIN_4") (pintype "input"))
    )
    (net (code "31") (name "Net-(U33-DOUT)") (class "Default")
      (node (ref "U33") (pin "2") (pinfunction "DOUT_2") (pintype "output"))
      (node (ref "U34") (pin "4") (pinfunction "DIN_4") (pintype "input"))
    )
    (net (code "32") (name "Net-(U34-DOUT)") (class "Default")
      (node (ref "U34") (pin "2") (pinfunction "DOUT_2") (pintype "output"))
      (node (ref "U35") (pin "4") (pinfunction "DIN_4") (pintype "input"))
    )
    (net (code "33") (name "Net-(U35-DOUT)") (class "Default")
      (node (ref "U35") (pin "2") (pinfunction "DOUT_2") (pintype "output"))
      (node (ref "U36") (pin "4") (pinfunction "DIN_4") (pintype "input"))
    )
    (net (code "34") (name "Net-(U36-DOUT)") (class "Default")
      (node (ref "U36") (pin "2") (pinfunction "DOUT_2") (pintype "output"))
      (node (ref "U37") (pin "4") (pinfunction "DIN_4") (pintype "input"))
    )
    (net (code "35") (name "Net-(U37-DOUT)") (class "Default")
      (node (ref "U37") (pin "2") (pinfunction "DOUT_2") (pintype "output"))
      (node (ref "U38") (pin "4") (pinfunction "DIN_4") (pintype "input"))
    )
    (net (code "36") (name "Net-(U38-DOUT)") (class "Default")
      (node (ref "U38") (pin "2") (pinfunction "DOUT_2") (pintype "output"))
      (node (ref "U39") (pin "4") (pinfunction "DIN_4") (pintype "input"))
    )
    (net (code "37") (name "Net-(U39-DOUT)") (class "Default")
      (node (ref "U39") (pin "2") (pinfunction "DOUT_2") (pintype "output"))
      (node (ref "U40") (pin "4") (pinfunction "DIN_4") (pintype "input"))
    )
    (net (code "38") (name "Net-(U40-DOUT)") (class "Default")
      (node (ref "U40") (pin "2") (pinfunction "DOUT_2") (pintype "output"))
      (node (ref "U41") (pin "4") (pinfunction "DIN_4") (pintype "input"))
    )
    (net (code "39") (name "Net-(U41-DOUT)") (class "Default")
      (node (ref "U41") (pin "2") (pinfunction "DOUT_2") (pintype "output"))
      (node (ref "U42") (pin "4") (pinfunction "DIN_4") (pintype "input"))
    )
    (net (code "40") (name "Net-(U42-DOUT)") (class "Default")
      (node (ref "U42") (pin "2") (pinfunction "DOUT_2") (pintype "output"))
      (node (ref "U43") (pin "4") (pinfunction "DIN_4") (pintype "input"))
    )
    (net (code "41") (name "Net-(U43-DOUT)") (class "Default")
      (node (ref "U43") (pin "2") (pinfunction "DOUT_2") (pintype "output"))
      (node (ref "U44") (pin "4") (pinfunction "DIN_4") (pintype "input"))
    )
    (net (code "42") (name "Net-(U44-DOUT)") (class "Default")
      (node (ref "U44") (pin "2") (pinfunction "DOUT_2") (pintype "output"))
      (node (ref "U45") (pin "4") (pinfunction "DIN_4") (pintype "input"))
    )
    (net (code "43") (name "Net-(U45-DOUT)") (class "Default")
      (node (ref "U45") (pin "2") (pinfunction "DOUT_2") (pintype "output"))
      (node (ref "U46") (pin "4") (pinfunction "DIN_4") (pintype "input"))
    )
    (net (code "44") (name "Net-(U46-DOUT)") (class "Default")
      (node (ref "U46") (pin "2") (pinfunction "DOUT_2") (pintype "output"))
      (node (ref "U47") (pin "4") (pinfunction "DIN_4") (pintype "input"))
    )
    (net (code "45") (name "Net-(U47-DOUT)") (class "Default")
      (node (ref "U47") (pin "2") (pinfunction "DOUT_2") (pintype "output"))
      (node (ref "U48") (pin "4") (pinfunction "DIN_4") (pintype "input"))
    )
    (net (code "46") (name "Net-(U48-DOUT)") (class "Default")
      (node (ref "U48") (pin "2") (pinfunction "DOUT_2") (pintype "output"))
      (node (ref "U49") (pin "4") (pinfunction "DIN_4") (pintype "input"))
    )
    (net (code "47") (name "Net-(U49-DOUT)") (class "Default")
      (node (ref "U49") (pin "2") (pinfunction "DOUT_2") (pintype "output"))
      (node (ref "U50") (pin "4") (pinfunction "DIN_4") (pintype "input"))
    )
    (net (code "48") (name "Net-(U50-DOUT)") (class "Default")
      (node (ref "U50") (pin "2") (pinfunction "DOUT_2") (pintype "output"))
      (node (ref "U51") (pin "4") (pinfunction "DIN_4") (pintype "input"))
    )
    (net (code "49") (name "Net-(U51-DOUT)") (class "Default")
      (node (ref "U51") (pin "2") (pinfunction "DOUT_2") (pintype "output"))
      (node (ref "U52") (pin "4") (pinfunction "DIN_4") (pintype "input"))
    )
    (net (code "50") (name "Net-(U52-DOUT)") (class "Default")
      (node (ref "U52") (pin "2") (pinfunction "DOUT_2") (pintype "output"))
      (node (ref "U53") (pin "4") (pinfunction "DIN_4") (pintype "input"))
    )
    (net (code "51") (name "Net-(U53-DOUT)") (class "Default")
      (node (ref "U53") (pin "2") (pinfunction "DOUT_2") (pintype "output"))
      (node (ref "U54") (pin "4") (pinfunction "DIN_4") (pintype "input"))
    )
    (net (code "52") (name "Net-(U54-DOUT)") (class "Default")
      (node (ref "U54") (pin "2") (pinfunction "DOUT_2") (pintype "output"))
      (node (ref "U55") (pin "4") (pinfunction "DIN_4") (pintype "input"))
    )
    (net (code "53") (name "Net-(U55-DOUT)") (class "Default")
      (node (ref "U55") (pin "2") (pinfunction "DOUT_2") (pintype "output"))
      (node (ref "U56") (pin "4") (pinfunction "DIN_4") (pintype "input"))
    )
    (net (code "54") (name "Net-(U56-DOUT)") (class "Default")
      (node (ref "U56") (pin "2") (pinfunction "DOUT_2") (pintype "output"))
      (node (ref "U57") (pin "4") (pinfunction "DIN_4") (pintype "input"))
    )
    (net (code "55") (name "Net-(U57-DOUT)") (class "Default")
      (node (ref "U57") (pin "2") (pinfunction "DOUT_2") (pintype "output"))
      (node (ref "U58") (pin "4") (pinfunction "DIN_4") (pintype "input"))
    )
    (net (code "56") (name "Net-(U58-DOUT)") (class "Default")
      (node (ref "U58") (pin "2") (pinfunction "DOUT_2") (pintype "output"))
      (node (ref "U59") (pin "4") (pinfunction "DIN_4") (pintype "input"))
    )
    (net (code "57") (name "Net-(U59-DOUT)") (class "Default")
      (node (ref "U59") (pin "2") (pinfunction "DOUT_2") (pintype "output"))
      (node (ref "U60") (pin "4") (pinfunction "DIN_4") (pintype "input"))
    )
    (net (code "58") (name "Net-(U60-DOUT)") (class "Default")
      (node (ref "U60") (pin "2") (pinfunction "DOUT_2") (pintype "output"))
      (node (ref "U61") (pin "4") (pinfunction "DIN_4") (pintype "input"))
    )
    (net (code "59") (name "Net-(U61-DOUT)") (class "Default")
      (node (ref "U61") (pin "2") (pinfunction "DOUT_2") (pintype "output"))
      (node (ref "U62") (pin "4") (pinfunction "DIN_4") (pintype "input"))
    )
    (net (code "60") (name "Net-(U62-DOUT)") (class "Default")
      (node (ref "U62") (pin "2") (pinfunction "DOUT_2") (pintype "output"))
      (node (ref "U63") (pin "4") (pinfunction "DIN_4") (pintype "input"))
    )
    (net (code "61") (name "Net-(U63-DOUT)") (class "Default")
      (node (ref "U63") (pin "2") (pinfunction "DOUT_2") (pintype "output"))
      (node (ref "U64") (pin "4") (pinfunction "DIN_4") (pintype "input"))
    )
    (net (code "62") (name "Net-(U64-DOUT)") (class "Default")
      (node (ref "U64") (pin "2") (pinfunction "DOUT_2") (pintype "output"))
      (node (ref "U65") (pin "4") (pinfunction "DIN_4") (pintype "input"))
    )
    (net (code "63") (name "Net-(U65-DOUT)") (class "Default")
      (node (ref "U65") (pin "2") (pinfunction "DOUT_2") (pintype "output"))
      (node (ref "U66") (pin "4") (pinfunction "DIN_4") (pintype "input"))
    )
    (net (code "64") (name "Net-(U66-DOUT)") (class "Default")
      (node (ref "U66") (pin "2") (pinfunction "DOUT_2") (pintype "output"))
      (node (ref "U67") (pin "4") (pinfunction "DIN_4") (pintype "input"))
    )
    (net (code "65") (name "Net-(U67-DOUT)") (class "Default")
      (node (ref "U67") (pin "2") (pinfunction "DOUT_2") (pintype "output"))
      (node (ref "U68") (pin "4") (pinfunction "DIN_4") (pintype "input"))
    )
    (net (code "66") (name "Net-(U68-DOUT)") (class "Default")
      (node (ref "U68") (pin "2") (pinfunction "DOUT_2") (pintype "output"))
      (node (ref "U69") (pin "4") (pinfunction "DIN_4") (pintype "input"))
    )
    (net (code "67") (name "unconnected-(U69-DOUT-Pad2)") (class "Default")
      (node (ref "U69") (pin "2") (pinfunction "DOUT_2") (pintype "output+no_connect"))
    )
  )
)
